# thermal_actuator_v1_0.net
KiCad netlist of a schematic drawn in EAGLE
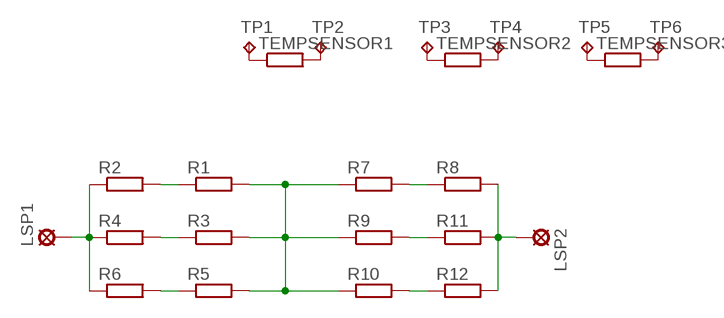
[diagram p0: schematic, sheet 1]

(export (version "E")
  (design (tool "Eeschema 10.0.6"))
  (components
    (comp (ref "LSP1")
      (value "LSP10")
      (footprint "eagle-import:LSP10")
      (libsource (lib "eagle-import") (part "LSP10"))
    )
    (comp (ref "LSP2")
      (value "LSP10")
      (footprint "eagle-import:LSP10")
      (libsource (lib "eagle-import") (part "LSP10"))
    )
    (comp (ref "R1")
      (value "R-EU_R0402")
      (footprint "eagle-import:R0402")
      (libsource (lib "eagle-import") (part "R-EU_R0402"))
    )
    (comp (ref "R2")
      (value "R-EU_R0402")
      (footprint "eagle-import:R0402")
      (libsource (lib "eagle-import") (part "R-EU_R0402"))
    )
    (comp (ref "R3")
      (value "R-EU_R0402")
      (footprint "eagle-import:R0402")
      (libsource (lib "eagle-import") (part "R-EU_R0402"))
    )
    (comp (ref "R4")
      (value "R-EU_R0402")
      (footprint "eagle-import:R0402")
      (libsource (lib "eagle-import") (part "R-EU_R0402"))
    )
    (comp (ref "R5")
      (value "R-EU_R0402")
      (footprint "eagle-import:R0402")
      (libsource (lib "eagle-import") (part "R-EU_R0402"))
    )
    (comp (ref "R6")
      (value "R-EU_R0402")
      (footprint "eagle-import:R0402")
      (libsource (lib "eagle-import") (part "R-EU_R0402"))
    )
    (comp (ref "R7")
      (value "R-EU_R0402")
      (footprint "eagle-import:R0402")
      (libsource (lib "eagle-import") (part "R-EU_R0402"))
    )
    (comp (ref "R8")
      (value "R-EU_R0402")
      (footprint "eagle-import:R0402")
      (libsource (lib "eagle-import") (part "R-EU_R0402"))
    )
    (comp (ref "R9")
      (value "R-EU_R0402")
      (footprint "eagle-import:R0402")
      (libsource (lib "eagle-import") (part "R-EU_R0402"))
    )
    (comp (ref "R10")
      (value "R-EU_R0402")
      (footprint "eagle-import:R0402")
      (libsource (lib "eagle-import") (part "R-EU_R0402"))
    )
    (comp (ref "R11")
      (value "R-EU_R0402")
      (footprint "eagle-import:R0402")
      (libsource (lib "eagle-import") (part "R-EU_R0402"))
    )
    (comp (ref "R12")
      (value "R-EU_R0402")
      (footprint "eagle-import:R0402")
      (libsource (lib "eagle-import") (part "R-EU_R0402"))
    )
    (comp (ref "TEMPSENSOR1")
      (value "R-EU_R0402")
      (footprint "eagle-import:R0402")
      (libsource (lib "eagle-import") (part "R-EU_R0402"))
    )
    (comp (ref "TEMPSENSOR2")
      (value "R-EU_R0402")
      (footprint "eagle-import:R0402")
      (libsource (lib "eagle-import") (part "R-EU_R0402"))
    )
    (comp (ref "TEMPSENSOR3")
      (value "R-EU_R0402")
      (footprint "eagle-import:R0402")
      (libsource (lib "eagle-import") (part "R-EU_R0402"))
    )
    (comp (ref "TP1")
      (value "TPTP10R")
      (footprint "eagle-import:TP10R")
      (libsource (lib "eagle-import") (part "TPTP10R"))
    )
    (comp (ref "TP2")
      (value "TPTP10R")
      (footprint "eagle-import:TP10R")
      (libsource (lib "eagle-import") (part "TPTP10R"))
    )
    (comp (ref "TP3")
      (value "TPTP10R")
      (footprint "eagle-import:TP10R")
      (libsource (lib "eagle-import") (part "TPTP10R"))
    )
    (comp (ref "TP4")
      (value "TPTP10R")
      (footprint "eagle-import:TP10R")
      (libsource (lib "eagle-import") (part "TPTP10R"))
    )
    (comp (ref "TP5")
      (value "TPTP10R")
      (footprint "eagle-import:TP10R")
      (libsource (lib "eagle-import") (part "TPTP10R"))
    )
    (comp (ref "TP6")
      (value "TPTP10R")
      (footprint "eagle-import:TP10R")
      (libsource (lib "eagle-import") (part "TPTP10R"))
    )
  )
  (nets
    (net (code "1") (name "Net-(LSP1-PadMP)") (class "Default")
      (node (ref "LSP1") (pin "MP") (pinfunction "MP_MP") (pintype "passive"))
      (node (ref "R2") (pin "1") (pinfunction "1_1") (pintype "passive"))
      (node (ref "R4") (pin "1") (pinfunction "1_1") (pintype "passive"))
      (node (ref "R6") (pin "1") (pinfunction "1_1") (pintype "passive"))
    )
    (net (code "2") (name "Net-(LSP2-PadMP)") (class "Default")
      (node (ref "LSP2") (pin "MP") (pinfunction "MP_MP") (pintype "passive"))
      (node (ref "R11") (pin "2") (pinfunction "2_2") (pintype "passive"))
      (node (ref "R12") (pin "2") (pinfunction "2_2") (pintype "passive"))
      (node (ref "R8") (pin "2") (pinfunction "2_2") (pintype "passive"))
    )
    (net (code "3") (name "Net-(R1-Pad1)") (class "Default")
      (node (ref "R1") (pin "1") (pinfunction "1_1") (pintype "passive"))
      (node (ref "R2") (pin "2") (pinfunction "2_2") (pintype "passive"))
    )
    (net (code "4") (name "Net-(R1-Pad2)") (class "Default")
      (node (ref "R1") (pin "2") (pinfunction "2_2") (pintype "passive"))
      (node (ref "R10") (pin "1") (pinfunction "1_1") (pintype "passive"))
      (node (ref "R3") (pin "2") (pinfunction "2_2") (pintype "passive"))
      (node (ref "R5") (pin "2") (pinfunction "2_2") (pintype "passive"))
      (node (ref "R7") (pin "1") (pinfunction "1_1") (pintype "passive"))
      (node (ref "R9") (pin "1") (pinfunction "1_1") (pintype "passive"))
    )
    (net (code "5") (name "Net-(R3-Pad1)") (class "Default")
      (node (ref "R3") (pin "1") (pinfunction "1_1") (pintype "passive"))
      (node (ref "R4") (pin "2") (pinfunction "2_2") (pintype "passive"))
    )
    (net (code "6") (name "Net-(R5-Pad1)") (class "Default")
      (node (ref "R5") (pin "1") (pinfunction "1_1") (pintype "passive"))
      (node (ref "R6") (pin "2") (pinfunction "2_2") (pintype "passive"))
    )
    (net (code "7") (name "Net-(R7-Pad2)") (class "Default")
      (node (ref "R7") (pin "2") (pinfunction "2_2") (pintype "passive"))
      (node (ref "R8") (pin "1") (pinfunction "1_1") (pintype "passive"))
    )
    (net (code "8") (name "Net-(R10-Pad2)") (class "Default")
      (node (ref "R10") (pin "2") (pinfunction "2_2") (pintype "passive"))
      (node (ref "R12") (pin "1") (pinfunction "1_1") (pintype "passive"))
    )
    (net (code "9") (name "Net-(R11-Pad1)") (class "Default")
      (node (ref "R11") (pin "1") (pinfunction "1_1") (pintype "passive"))
      (node (ref "R9") (pin "2") (pinfunction "2_2") (pintype "passive"))
    )
    (net (code "10") (name "Net-(TEMPSENSOR1-Pad1)") (class "Default")
      (node (ref "TEMPSENSOR1") (pin "1") (pinfunction "1_1") (pintype "passive"))
      (node (ref "TP1") (pin "TP") (pinfunction "TP_TP") (pintype "input"))
    )
    (net (code "11") (name "Net-(TEMPSENSOR1-Pad2)") (class "Default")
      (node (ref "TEMPSENSOR1") (pin "2") (pinfunction "2_2") (pintype "passive"))
      (node (ref "TP2") (pin "TP") (pinfunction "TP_TP") (pintype "input"))
    )
    (net (code "12") (name "Net-(TEMPSENSOR2-Pad1)") (class "Default")
      (node (ref "TEMPSENSOR2") (pin "1") (pinfunction "1_1") (pintype "passive"))
      (node (ref "TP3") (pin "TP") (pinfunction "TP_TP") (pintype "input"))
    )
    (net (code "13") (name "Net-(TEMPSENSOR2-Pad2)") (class "Default")
      (node (ref "TEMPSENSOR2") (pin "2") (pinfunction "2_2") (pintype "passive"))
      (node (ref "TP4") (pin "TP") (pinfunction "TP_TP") (pintype "input"))
    )
    (net (code "14") (name "Net-(TEMPSENSOR3-Pad1)") (class "Default")
      (node (ref "TEMPSENSOR3") (pin "1") (pinfunction "1_1") (pintype "passive"))
      (node (ref "TP5") (pin "TP") (pinfunction "TP_TP") (pintype "input"))
    )
    (net (code "15") (name "Net-(TEMPSENSOR3-Pad2)") (class "Default")
      (node (ref "TEMPSENSOR3") (pin "2") (pinfunction "2_2") (pintype "passive"))
      (node (ref "TP6") (pin "TP") (pinfunction "TP_TP") (pintype "input"))
    )
  )
)
